# Esquematico_Uno.net
KiCad netlist of a schematic drawn in EAGLE
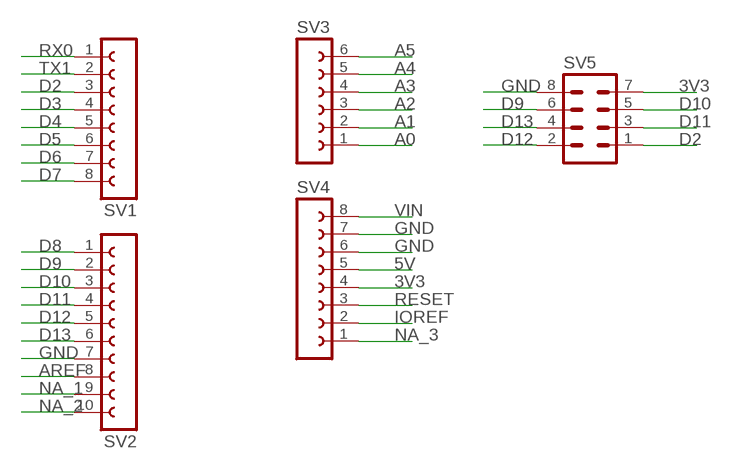
[diagram p0: schematic, sheet 1]

(export (version "E")
  (design (tool "Eeschema 10.0.6"))
  (components
    (comp (ref "SV1")
      (value "FE08-1")
      (footprint "eagle-import:FE08")
      (libsource (lib "eagle-import") (part "FE08-1"))
    )
    (comp (ref "SV2")
      (value "FE10-1")
      (footprint "eagle-import:FE10")
      (libsource (lib "eagle-import") (part "FE10-1"))
    )
    (comp (ref "SV3")
      (value "FE06-1")
      (footprint "eagle-import:FE06")
      (libsource (lib "eagle-import") (part "FE06-1"))
    )
    (comp (ref "SV4")
      (value "FE08-1")
      (footprint "eagle-import:FE08")
      (libsource (lib "eagle-import") (part "FE08-1"))
    )
    (comp (ref "SV5")
      (value "MA04-2")
      (footprint "eagle-import:MA04-2")
      (libsource (lib "eagle-import") (part "MA04-2"))
    )
  )
  (nets
    (net (code "1") (name "/3V3") (class "Default")
      (node (ref "SV4") (pin "4") (pinfunction "4_4") (pintype "passive"))
      (node (ref "SV5") (pin "7") (pinfunction "7_7") (pintype "passive"))
    )
    (net (code "2") (name "/5V") (class "Default")
      (node (ref "SV4") (pin "5") (pinfunction "5_5") (pintype "passive"))
    )
    (net (code "3") (name "/A0") (class "Default")
      (node (ref "SV3") (pin "1") (pinfunction "1_1") (pintype "passive"))
    )
    (net (code "4") (name "/A1") (class "Default")
      (node (ref "SV3") (pin "2") (pinfunction "2_2") (pintype "passive"))
    )
    (net (code "5") (name "/A2") (class "Default")
      (node (ref "SV3") (pin "3") (pinfunction "3_3") (pintype "passive"))
    )
    (net (code "6") (name "/A3") (class "Default")
      (node (ref "SV3") (pin "4") (pinfunction "4_4") (pintype "passive"))
    )
    (net (code "7") (name "/A4") (class "Default")
      (node (ref "SV3") (pin "5") (pinfunction "5_5") (pintype "passive"))
    )
    (net (code "8") (name "/A5") (class "Default")
      (node (ref "SV3") (pin "6") (pinfunction "6_6") (pintype "passive"))
    )
    (net (code "9") (name "/AREF") (class "Default")
      (node (ref "SV2") (pin "8") (pinfunction "8_8") (pintype "passive"))
    )
    (net (code "10") (name "/D2") (class "Default")
      (node (ref "SV1") (pin "3") (pinfunction "3_3") (pintype "passive"))
      (node (ref "SV5") (pin "1") (pinfunction "1_1") (pintype "passive"))
    )
    (net (code "11") (name "/D3") (class "Default")
      (node (ref "SV1") (pin "4") (pinfunction "4_4") (pintype "passive"))
    )
    (net (code "12") (name "/D4") (class "Default")
      (node (ref "SV1") (pin "5") (pinfunction "5_5") (pintype "passive"))
    )
    (net (code "13") (name "/D5") (class "Default")
      (node (ref "SV1") (pin "6") (pinfunction "6_6") (pintype "passive"))
    )
    (net (code "14") (name "/D6") (class "Default")
      (node (ref "SV1") (pin "7") (pinfunction "7_7") (pintype "passive"))
    )
    (net (code "15") (name "/D7") (class "Default")
      (node (ref "SV1") (pin "8") (pinfunction "8_8") (pintype "passive"))
    )
    (net (code "16") (name "/D8") (class "Default")
      (node (ref "SV2") (pin "1") (pinfunction "1_1") (pintype "passive"))
    )
    (net (code "17") (name "/D9") (class "Default")
      (node (ref "SV2") (pin "2") (pinfunction "2_2") (pintype "passive"))
      (node (ref "SV5") (pin "6") (pinfunction "6_6") (pintype "passive"))
    )
    (net (code "18") (name "/D10") (class "Default")
      (node (ref "SV2") (pin "3") (pinfunction "3_3") (pintype "passive"))
      (node (ref "SV5") (pin "5") (pinfunction "5_5") (pintype "passive"))
    )
    (net (code "19") (name "/D11") (class "Default")
      (node (ref "SV2") (pin "4") (pinfunction "4_4") (pintype "passive"))
      (node (ref "SV5") (pin "3") (pinfunction "3_3") (pintype "passive"))
    )
    (net (code "20") (name "/D12") (class "Default")
      (node (ref "SV2") (pin "5") (pinfunction "5_5") (pintype "passive"))
      (node (ref "SV5") (pin "2") (pinfunction "2_2") (pintype "passive"))
    )
    (net (code "21") (name "/D13") (class "Default")
      (node (ref "SV2") (pin "6") (pinfunction "6_6") (pintype "passive"))
      (node (ref "SV5") (pin "4") (pinfunction "4_4") (pintype "passive"))
    )
    (net (code "22") (name "/GND") (class "Default")
      (node (ref "SV2") (pin "7") (pinfunction "7_7") (pintype "passive"))
      (node (ref "SV4") (pin "6") (pinfunction "6_6") (pintype "passive"))
      (node (ref "SV4") (pin "7") (pinfunction "7_7") (pintype "passive"))
      (node (ref "SV5") (pin "8") (pinfunction "8_8") (pintype "passive"))
    )
    (net (code "23") (name "/IOREF") (class "Default")
      (node (ref "SV4") (pin "2") (pinfunction "2_2") (pintype "passive"))
    )
    (net (code "24") (name "/NA_1") (class "Default")
      (node (ref "SV2") (pin "9") (pinfunction "9_9") (pintype "passive"))
    )
    (net (code "25") (name "/NA_2") (class "Default")
      (node (ref "SV2") (pin "10") (pinfunction "10_10") (pintype "passive"))
    )
    (net (code "26") (name "/NA_3") (class "Default")
      (node (ref "SV4") (pin "1") (pinfunction "1_1") (pintype "passive"))
    )
    (net (code "27") (name "/RESET") (class "Default")
      (node (ref "SV4") (pin "3") (pinfunction "3_3") (pintype "passive"))
    )
    (net (code "28") (name "/RX0") (class "Default")
      (node (ref "SV1") (pin "1") (pinfunction "1_1") (pintype "passive"))
    )
    (net (code "29") (name "/TX1") (class "Default")
      (node (ref "SV1") (pin "2") (pinfunction "2_2") (pintype "passive"))
    )
    (net (code "30") (name "/VIN") (class "Default")
      (node (ref "SV4") (pin "8") (pinfunction "8_8") (pintype "passive"))
    )
  )
)
